# 06_-_NEON.net
KiCad netlist of a schematic drawn in Altium Designer
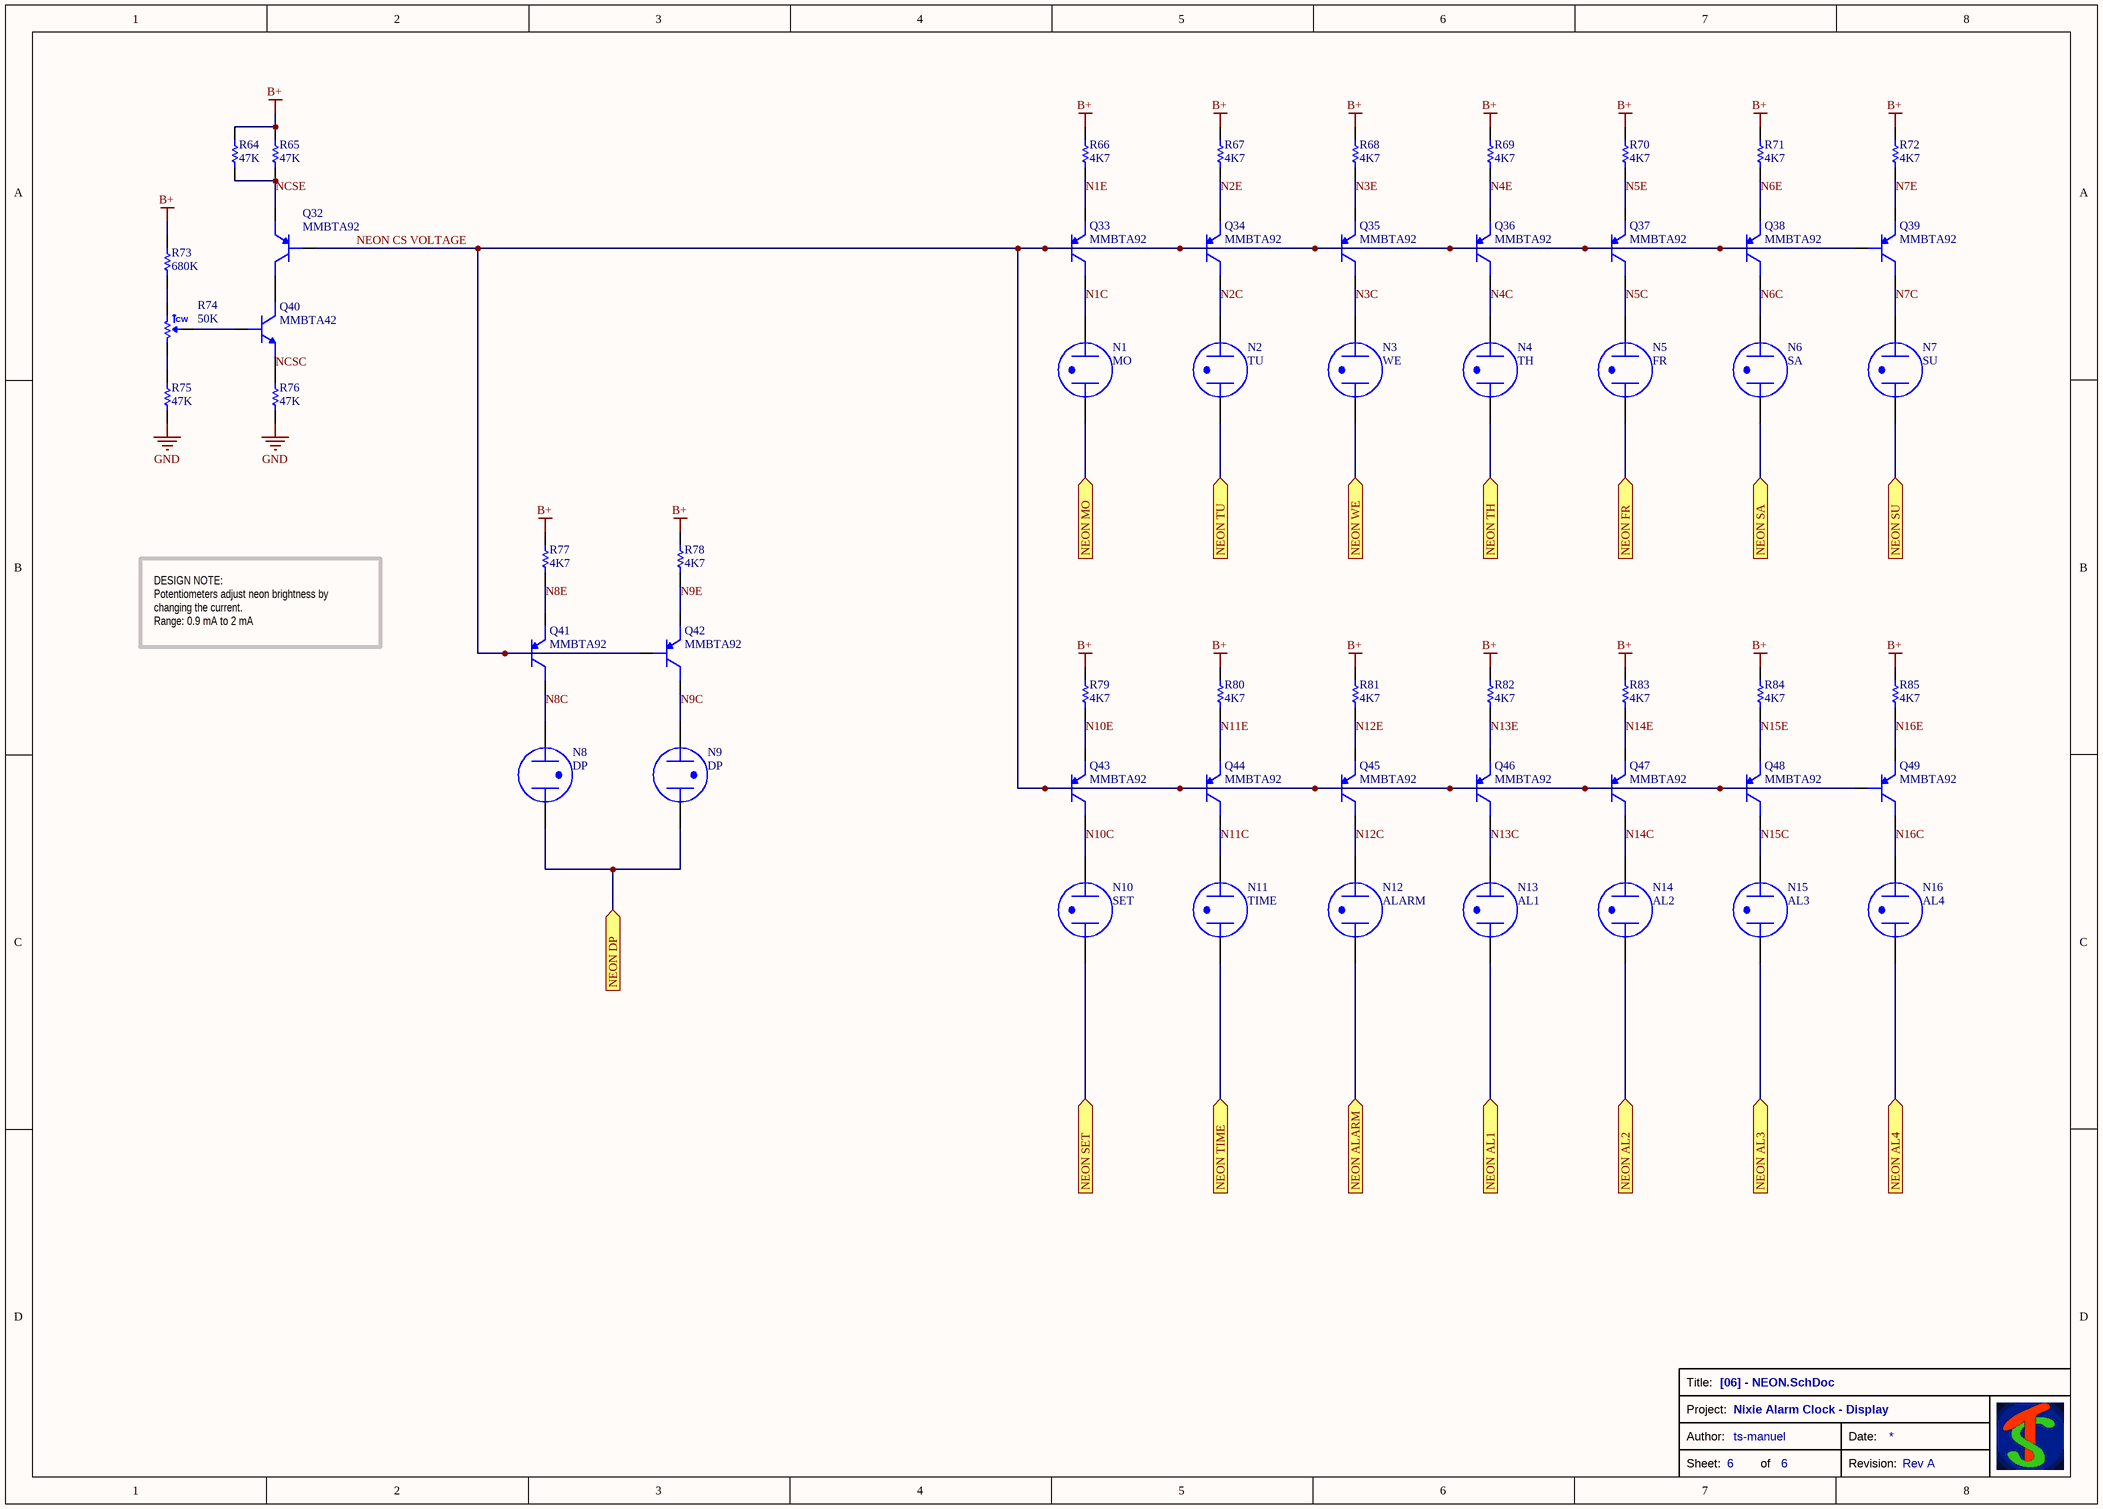
[diagram p0: [06] - NEON.SchDoc]

(export (version "E")
  (design (tool "Eeschema 10.0.6"))
  (components
    (comp (ref "N1")
      (value "MO")
      (footprint "NE4 NEON LAMP")
      (description "Lampade Std. Brightness Neon Lamp Tin Leads")
      (libsource (lib "mt_local_library") (part "T4-NEON-LAMP"))
    )
    (comp (ref "N2")
      (value "TU")
      (footprint "NE4 NEON LAMP")
      (description "Lampade Std. Brightness Neon Lamp Tin Leads")
      (libsource (lib "mt_local_library") (part "T4-NEON-LAMP"))
    )
    (comp (ref "N3")
      (value "WE")
      (footprint "NE4 NEON LAMP")
      (description "Lampade Std. Brightness Neon Lamp Tin Leads")
      (libsource (lib "mt_local_library") (part "T4-NEON-LAMP"))
    )
    (comp (ref "N4")
      (value "TH")
      (footprint "NE4 NEON LAMP")
      (description "Lampade Std. Brightness Neon Lamp Tin Leads")
      (libsource (lib "mt_local_library") (part "T4-NEON-LAMP"))
    )
    (comp (ref "N5")
      (value "FR")
      (footprint "NE4 NEON LAMP")
      (description "Lampade Std. Brightness Neon Lamp Tin Leads")
      (libsource (lib "mt_local_library") (part "T4-NEON-LAMP"))
    )
    (comp (ref "N6")
      (value "SA")
      (footprint "NE4 NEON LAMP")
      (description "Lampade Std. Brightness Neon Lamp Tin Leads")
      (libsource (lib "mt_local_library") (part "T4-NEON-LAMP"))
    )
    (comp (ref "N7")
      (value "SU")
      (footprint "NE4 NEON LAMP")
      (description "Lampade Std. Brightness Neon Lamp Tin Leads")
      (libsource (lib "mt_local_library") (part "T4-NEON-LAMP"))
    )
    (comp (ref "N8")
      (value "DP")
      (footprint "NE4 NEON LAMP")
      (description "Lampade Std. Brightness Neon Lamp Tin Leads")
      (libsource (lib "mt_local_library") (part "T4-NEON-LAMP"))
    )
    (comp (ref "N9")
      (value "DP")
      (footprint "NE4 NEON LAMP")
      (description "Lampade Std. Brightness Neon Lamp Tin Leads")
      (libsource (lib "mt_local_library") (part "T4-NEON-LAMP"))
    )
    (comp (ref "N10")
      (value "SET")
      (footprint "NE4 NEON LAMP")
      (description "Lampade Std. Brightness Neon Lamp Tin Leads")
      (libsource (lib "mt_local_library") (part "T4-NEON-LAMP"))
    )
    (comp (ref "N11")
      (value "TIME")
      (footprint "NE4 NEON LAMP")
      (description "Lampade Std. Brightness Neon Lamp Tin Leads")
      (libsource (lib "mt_local_library") (part "T4-NEON-LAMP"))
    )
    (comp (ref "N12")
      (value "ALARM")
      (footprint "NE4 NEON LAMP")
      (description "Lampade Std. Brightness Neon Lamp Tin Leads")
      (libsource (lib "mt_local_library") (part "T4-NEON-LAMP"))
    )
    (comp (ref "N13")
      (value "AL1")
      (footprint "NE4 NEON LAMP")
      (description "Lampade Std. Brightness Neon Lamp Tin Leads")
      (libsource (lib "mt_local_library") (part "T4-NEON-LAMP"))
    )
    (comp (ref "N14")
      (value "AL2")
      (footprint "NE4 NEON LAMP")
      (description "Lampade Std. Brightness Neon Lamp Tin Leads")
      (libsource (lib "mt_local_library") (part "T4-NEON-LAMP"))
    )
    (comp (ref "N15")
      (value "AL3")
      (footprint "NE4 NEON LAMP")
      (description "Lampade Std. Brightness Neon Lamp Tin Leads")
      (libsource (lib "mt_local_library") (part "T4-NEON-LAMP"))
    )
    (comp (ref "N16")
      (value "AL4")
      (footprint "NE4 NEON LAMP")
      (description "Lampade Std. Brightness Neon Lamp Tin Leads")
      (libsource (lib "mt_local_library") (part "T4-NEON-LAMP"))
    )
    (comp (ref "Q32")
      (value "MMBTA92")
      (footprint "SOT95P240X110-3N")
      (description "300V PNP SMALL SIGNAL TRANSISTOR IN SOT23")
      (libsource (lib "mt_local_library") (part "PNP-MMBTA92"))
    )
    (comp (ref "Q33")
      (value "MMBTA92")
      (footprint "SOT95P240X110-3N")
      (description "300V PNP SMALL SIGNAL TRANSISTOR IN SOT23")
      (libsource (lib "mt_local_library") (part "PNP-MMBTA92"))
    )
    (comp (ref "Q34")
      (value "MMBTA92")
      (footprint "SOT95P240X110-3N")
      (description "300V PNP SMALL SIGNAL TRANSISTOR IN SOT23")
      (libsource (lib "mt_local_library") (part "PNP-MMBTA92"))
    )
    (comp (ref "Q35")
      (value "MMBTA92")
      (footprint "SOT95P240X110-3N")
      (description "300V PNP SMALL SIGNAL TRANSISTOR IN SOT23")
      (libsource (lib "mt_local_library") (part "PNP-MMBTA92"))
    )
    (comp (ref "Q36")
      (value "MMBTA92")
      (footprint "SOT95P240X110-3N")
      (description "300V PNP SMALL SIGNAL TRANSISTOR IN SOT23")
      (libsource (lib "mt_local_library") (part "PNP-MMBTA92"))
    )
    (comp (ref "Q37")
      (value "MMBTA92")
      (footprint "SOT95P240X110-3N")
      (description "300V PNP SMALL SIGNAL TRANSISTOR IN SOT23")
      (libsource (lib "mt_local_library") (part "PNP-MMBTA92"))
    )
    (comp (ref "Q38")
      (value "MMBTA92")
      (footprint "SOT95P240X110-3N")
      (description "300V PNP SMALL SIGNAL TRANSISTOR IN SOT23")
      (libsource (lib "mt_local_library") (part "PNP-MMBTA92"))
    )
    (comp (ref "Q39")
      (value "MMBTA92")
      (footprint "SOT95P240X110-3N")
      (description "300V PNP SMALL SIGNAL TRANSISTOR IN SOT23")
      (libsource (lib "mt_local_library") (part "PNP-MMBTA92"))
    )
    (comp (ref "Q40")
      (value "MMBTA42")
      (footprint "SOT95P240X110-3N")
      (description "300V NPN SMALL SIGNAL TRANSISTOR IN SOT23")
      (libsource (lib "mt_local_library") (part "NPN-MMBTA42"))
    )
    (comp (ref "Q41")
      (value "MMBTA92")
      (footprint "SOT95P240X110-3N")
      (description "300V PNP SMALL SIGNAL TRANSISTOR IN SOT23")
      (libsource (lib "mt_local_library") (part "PNP-MMBTA92"))
    )
    (comp (ref "Q42")
      (value "MMBTA92")
      (footprint "SOT95P240X110-3N")
      (description "300V PNP SMALL SIGNAL TRANSISTOR IN SOT23")
      (libsource (lib "mt_local_library") (part "PNP-MMBTA92"))
    )
    (comp (ref "Q43")
      (value "MMBTA92")
      (footprint "SOT95P240X110-3N")
      (description "300V PNP SMALL SIGNAL TRANSISTOR IN SOT23")
      (libsource (lib "mt_local_library") (part "PNP-MMBTA92"))
    )
    (comp (ref "Q44")
      (value "MMBTA92")
      (footprint "SOT95P240X110-3N")
      (description "300V PNP SMALL SIGNAL TRANSISTOR IN SOT23")
      (libsource (lib "mt_local_library") (part "PNP-MMBTA92"))
    )
    (comp (ref "Q45")
      (value "MMBTA92")
      (footprint "SOT95P240X110-3N")
      (description "300V PNP SMALL SIGNAL TRANSISTOR IN SOT23")
      (libsource (lib "mt_local_library") (part "PNP-MMBTA92"))
    )
    (comp (ref "Q46")
      (value "MMBTA92")
      (footprint "SOT95P240X110-3N")
      (description "300V PNP SMALL SIGNAL TRANSISTOR IN SOT23")
      (libsource (lib "mt_local_library") (part "PNP-MMBTA92"))
    )
    (comp (ref "Q47")
      (value "MMBTA92")
      (footprint "SOT95P240X110-3N")
      (description "300V PNP SMALL SIGNAL TRANSISTOR IN SOT23")
      (libsource (lib "mt_local_library") (part "PNP-MMBTA92"))
    )
    (comp (ref "Q48")
      (value "MMBTA92")
      (footprint "SOT95P240X110-3N")
      (description "300V PNP SMALL SIGNAL TRANSISTOR IN SOT23")
      (libsource (lib "mt_local_library") (part "PNP-MMBTA92"))
    )
    (comp (ref "Q49")
      (value "MMBTA92")
      (footprint "SOT95P240X110-3N")
      (description "300V PNP SMALL SIGNAL TRANSISTOR IN SOT23")
      (libsource (lib "mt_local_library") (part "PNP-MMBTA92"))
    )
    (comp (ref "R64")
      (value "47K")
      (footprint "RES-0805")
      (description "Thin Film Resistors 1/8W 47K ohm 1% 50ppm")
      (fields (field (name "MANUFACTURER") "Yageo") (field (name "TOLERANCE") "1%"))
      (libsource (lib "mt_local_library") (part "RES-0805-47K-RT0805FRE0747KL"))
    )
    (comp (ref "R65")
      (value "47K")
      (footprint "RES-0805")
      (description "Thin Film Resistors 1/8W 47K ohm 1% 50ppm")
      (fields (field (name "MANUFACTURER") "Yageo") (field (name "TOLERANCE") "1%"))
      (libsource (lib "mt_local_library") (part "RES-0805-47K-RT0805FRE0747KL"))
    )
    (comp (ref "R66")
      (value "4K7")
      (footprint "RES-0805")
      (description "Thin Film Resistors 4.7K ohm 1% 50 ppm")
      (fields (field (name "MANUFACTURER") "Yageo") (field (name "TOLERANCE") "1%"))
      (libsource (lib "mt_local_library") (part "RES-0805-4K7-RT0805FRE134K7L"))
    )
    (comp (ref "R67")
      (value "4K7")
      (footprint "RES-0805")
      (description "Thin Film Resistors 4.7K ohm 1% 50 ppm")
      (fields (field (name "MANUFACTURER") "Yageo") (field (name "TOLERANCE") "1%"))
      (libsource (lib "mt_local_library") (part "RES-0805-4K7-RT0805FRE134K7L"))
    )
    (comp (ref "R68")
      (value "4K7")
      (footprint "RES-0805")
      (description "Thin Film Resistors 4.7K ohm 1% 50 ppm")
      (fields (field (name "MANUFACTURER") "Yageo") (field (name "TOLERANCE") "1%"))
      (libsource (lib "mt_local_library") (part "RES-0805-4K7-RT0805FRE134K7L"))
    )
    (comp (ref "R69")
      (value "4K7")
      (footprint "RES-0805")
      (description "Thin Film Resistors 4.7K ohm 1% 50 ppm")
      (fields (field (name "MANUFACTURER") "Yageo") (field (name "TOLERANCE") "1%"))
      (libsource (lib "mt_local_library") (part "RES-0805-4K7-RT0805FRE134K7L"))
    )
    (comp (ref "R70")
      (value "4K7")
      (footprint "RES-0805")
      (description "Thin Film Resistors 4.7K ohm 1% 50 ppm")
      (fields (field (name "MANUFACTURER") "Yageo") (field (name "TOLERANCE") "1%"))
      (libsource (lib "mt_local_library") (part "RES-0805-4K7-RT0805FRE134K7L"))
    )
    (comp (ref "R71")
      (value "4K7")
      (footprint "RES-0805")
      (description "Thin Film Resistors 4.7K ohm 1% 50 ppm")
      (fields (field (name "MANUFACTURER") "Yageo") (field (name "TOLERANCE") "1%"))
      (libsource (lib "mt_local_library") (part "RES-0805-4K7-RT0805FRE134K7L"))
    )
    (comp (ref "R72")
      (value "4K7")
      (footprint "RES-0805")
      (description "Thin Film Resistors 4.7K ohm 1% 50 ppm")
      (fields (field (name "MANUFACTURER") "Yageo") (field (name "TOLERANCE") "1%"))
      (libsource (lib "mt_local_library") (part "RES-0805-4K7-RT0805FRE134K7L"))
    )
    (comp (ref "R73")
      (value "680K")
      (footprint "RES-1206")
      (description "Thin Film Resistors 680K OHM 1% 50PPM 1/4W")
      (fields (field (name "MANUFACTURER") "Yageo") (field (name "TOLERANCE") "1%"))
      (libsource (lib "mt_local_library") (part "RES-1206-680K-RT1206FRE07680KL"))
    )
    (comp (ref "R74")
      (value "50K")
      (footprint "TC33X2503E")
      (description "Resistenze trimmer - SMD 3MM 50KOHMS 25% 0.1WATT OPEN FRM")
      (fields (field (name "MANUFACTURER") "Yageo") (field (name "TOLERANCE") "1%"))
      (libsource (lib "mt_local_library") (part "POT-50K-TC33X-2-503E"))
    )
    (comp (ref "R75")
      (value "47K")
      (footprint "RES-0805")
      (description "Thin Film Resistors 1/8W 47K ohm 1% 50ppm")
      (fields (field (name "MANUFACTURER") "Yageo") (field (name "TOLERANCE") "1%"))
      (libsource (lib "mt_local_library") (part "RES-0805-47K-RT0805FRE0747KL"))
    )
    (comp (ref "R76")
      (value "47K")
      (footprint "RES-0805")
      (description "Thin Film Resistors 1/8W 47K ohm 1% 50ppm")
      (fields (field (name "MANUFACTURER") "Yageo") (field (name "TOLERANCE") "1%"))
      (libsource (lib "mt_local_library") (part "RES-0805-47K-RT0805FRE0747KL"))
    )
    (comp (ref "R77")
      (value "4K7")
      (footprint "RES-0805")
      (description "Thin Film Resistors 4.7K ohm 1% 50 ppm")
      (fields (field (name "MANUFACTURER") "Yageo") (field (name "TOLERANCE") "1%"))
      (libsource (lib "mt_local_library") (part "RES-0805-4K7-RT0805FRE134K7L"))
    )
    (comp (ref "R78")
      (value "4K7")
      (footprint "RES-0805")
      (description "Thin Film Resistors 4.7K ohm 1% 50 ppm")
      (fields (field (name "MANUFACTURER") "Yageo") (field (name "TOLERANCE") "1%"))
      (libsource (lib "mt_local_library") (part "RES-0805-4K7-RT0805FRE134K7L"))
    )
    (comp (ref "R79")
      (value "4K7")
      (footprint "RES-0805")
      (description "Thin Film Resistors 4.7K ohm 1% 50 ppm")
      (fields (field (name "MANUFACTURER") "Yageo") (field (name "TOLERANCE") "1%"))
      (libsource (lib "mt_local_library") (part "RES-0805-4K7-RT0805FRE134K7L"))
    )
    (comp (ref "R80")
      (value "4K7")
      (footprint "RES-0805")
      (description "Thin Film Resistors 4.7K ohm 1% 50 ppm")
      (fields (field (name "MANUFACTURER") "Yageo") (field (name "TOLERANCE") "1%"))
      (libsource (lib "mt_local_library") (part "RES-0805-4K7-RT0805FRE134K7L"))
    )
    (comp (ref "R81")
      (value "4K7")
      (footprint "RES-0805")
      (description "Thin Film Resistors 4.7K ohm 1% 50 ppm")
      (fields (field (name "MANUFACTURER") "Yageo") (field (name "TOLERANCE") "1%"))
      (libsource (lib "mt_local_library") (part "RES-0805-4K7-RT0805FRE134K7L"))
    )
    (comp (ref "R82")
      (value "4K7")
      (footprint "RES-0805")
      (description "Thin Film Resistors 4.7K ohm 1% 50 ppm")
      (fields (field (name "MANUFACTURER") "Yageo") (field (name "TOLERANCE") "1%"))
      (libsource (lib "mt_local_library") (part "RES-0805-4K7-RT0805FRE134K7L"))
    )
    (comp (ref "R83")
      (value "4K7")
      (footprint "RES-0805")
      (description "Thin Film Resistors 4.7K ohm 1% 50 ppm")
      (fields (field (name "MANUFACTURER") "Yageo") (field (name "TOLERANCE") "1%"))
      (libsource (lib "mt_local_library") (part "RES-0805-4K7-RT0805FRE134K7L"))
    )
    (comp (ref "R84")
      (value "4K7")
      (footprint "RES-0805")
      (description "Thin Film Resistors 4.7K ohm 1% 50 ppm")
      (fields (field (name "MANUFACTURER") "Yageo") (field (name "TOLERANCE") "1%"))
      (libsource (lib "mt_local_library") (part "RES-0805-4K7-RT0805FRE134K7L"))
    )
    (comp (ref "R85")
      (value "4K7")
      (footprint "RES-0805")
      (description "Thin Film Resistors 4.7K ohm 1% 50 ppm")
      (fields (field (name "MANUFACTURER") "Yageo") (field (name "TOLERANCE") "1%"))
      (libsource (lib "mt_local_library") (part "RES-0805-4K7-RT0805FRE134K7L"))
    )
  )
  (nets
    (net (code "1") (name "/N1C") (class "Default")
      (node (ref "N1") (pin "2") (pinfunction "2_2") (pintype "passive"))
      (node (ref "Q33") (pin "3") (pinfunction "C_3") (pintype "passive"))
    )
    (net (code "2") (name "/N1E") (class "Default")
      (node (ref "Q33") (pin "2") (pinfunction "E_2") (pintype "passive"))
      (node (ref "R66") (pin "1") (pinfunction "1_1") (pintype "passive"))
    )
    (net (code "3") (name "/N2C") (class "Default")
      (node (ref "N2") (pin "2") (pinfunction "2_2") (pintype "passive"))
      (node (ref "Q34") (pin "3") (pinfunction "C_3") (pintype "passive"))
    )
    (net (code "4") (name "/N2E") (class "Default")
      (node (ref "Q34") (pin "2") (pinfunction "E_2") (pintype "passive"))
      (node (ref "R67") (pin "1") (pinfunction "1_1") (pintype "passive"))
    )
    (net (code "5") (name "/N3C") (class "Default")
      (node (ref "N3") (pin "2") (pinfunction "2_2") (pintype "passive"))
      (node (ref "Q35") (pin "3") (pinfunction "C_3") (pintype "passive"))
    )
    (net (code "6") (name "/N3E") (class "Default")
      (node (ref "Q35") (pin "2") (pinfunction "E_2") (pintype "passive"))
      (node (ref "R68") (pin "1") (pinfunction "1_1") (pintype "passive"))
    )
    (net (code "7") (name "/N4C") (class "Default")
      (node (ref "N4") (pin "2") (pinfunction "2_2") (pintype "passive"))
      (node (ref "Q36") (pin "3") (pinfunction "C_3") (pintype "passive"))
    )
    (net (code "8") (name "/N4E") (class "Default")
      (node (ref "Q36") (pin "2") (pinfunction "E_2") (pintype "passive"))
      (node (ref "R69") (pin "1") (pinfunction "1_1") (pintype "passive"))
    )
    (net (code "9") (name "/N5C") (class "Default")
      (node (ref "N5") (pin "2") (pinfunction "2_2") (pintype "passive"))
      (node (ref "Q37") (pin "3") (pinfunction "C_3") (pintype "passive"))
    )
    (net (code "10") (name "/N5E") (class "Default")
      (node (ref "Q37") (pin "2") (pinfunction "E_2") (pintype "passive"))
      (node (ref "R70") (pin "1") (pinfunction "1_1") (pintype "passive"))
    )
    (net (code "11") (name "/N6C") (class "Default")
      (node (ref "N6") (pin "2") (pinfunction "2_2") (pintype "passive"))
      (node (ref "Q38") (pin "3") (pinfunction "C_3") (pintype "passive"))
    )
    (net (code "12") (name "/N6E") (class "Default")
      (node (ref "Q38") (pin "2") (pinfunction "E_2") (pintype "passive"))
      (node (ref "R71") (pin "1") (pinfunction "1_1") (pintype "passive"))
    )
    (net (code "13") (name "/N7C") (class "Default")
      (node (ref "N7") (pin "2") (pinfunction "2_2") (pintype "passive"))
      (node (ref "Q39") (pin "3") (pinfunction "C_3") (pintype "passive"))
    )
    (net (code "14") (name "/N7E") (class "Default")
      (node (ref "Q39") (pin "2") (pinfunction "E_2") (pintype "passive"))
      (node (ref "R72") (pin "1") (pinfunction "1_1") (pintype "passive"))
    )
    (net (code "15") (name "/N8C") (class "Default")
      (node (ref "N8") (pin "1") (pinfunction "1_1") (pintype "passive"))
      (node (ref "Q41") (pin "3") (pinfunction "C_3") (pintype "passive"))
    )
    (net (code "16") (name "/N8E") (class "Default")
      (node (ref "Q41") (pin "2") (pinfunction "E_2") (pintype "passive"))
      (node (ref "R77") (pin "1") (pinfunction "1_1") (pintype "passive"))
    )
    (net (code "17") (name "/N9C") (class "Default")
      (node (ref "N9") (pin "1") (pinfunction "1_1") (pintype "passive"))
      (node (ref "Q42") (pin "3") (pinfunction "C_3") (pintype "passive"))
    )
    (net (code "18") (name "/N9E") (class "Default")
      (node (ref "Q42") (pin "2") (pinfunction "E_2") (pintype "passive"))
      (node (ref "R78") (pin "1") (pinfunction "1_1") (pintype "passive"))
    )
    (net (code "19") (name "/N10C") (class "Default")
      (node (ref "N10") (pin "2") (pinfunction "2_2") (pintype "passive"))
      (node (ref "Q43") (pin "3") (pinfunction "C_3") (pintype "passive"))
    )
    (net (code "20") (name "/N10E") (class "Default")
      (node (ref "Q43") (pin "2") (pinfunction "E_2") (pintype "passive"))
      (node (ref "R79") (pin "1") (pinfunction "1_1") (pintype "passive"))
    )
    (net (code "21") (name "/N11C") (class "Default")
      (node (ref "N11") (pin "2") (pinfunction "2_2") (pintype "passive"))
      (node (ref "Q44") (pin "3") (pinfunction "C_3") (pintype "passive"))
    )
    (net (code "22") (name "/N11E") (class "Default")
      (node (ref "Q44") (pin "2") (pinfunction "E_2") (pintype "passive"))
      (node (ref "R80") (pin "1") (pinfunction "1_1") (pintype "passive"))
    )
    (net (code "23") (name "/N12C") (class "Default")
      (node (ref "N12") (pin "2") (pinfunction "2_2") (pintype "passive"))
      (node (ref "Q45") (pin "3") (pinfunction "C_3") (pintype "passive"))
    )
    (net (code "24") (name "/N12E") (class "Default")
      (node (ref "Q45") (pin "2") (pinfunction "E_2") (pintype "passive"))
      (node (ref "R81") (pin "1") (pinfunction "1_1") (pintype "passive"))
    )
    (net (code "25") (name "/N13C") (class "Default")
      (node (ref "N13") (pin "2") (pinfunction "2_2") (pintype "passive"))
      (node (ref "Q46") (pin "3") (pinfunction "C_3") (pintype "passive"))
    )
    (net (code "26") (name "/N13E") (class "Default")
      (node (ref "Q46") (pin "2") (pinfunction "E_2") (pintype "passive"))
      (node (ref "R82") (pin "1") (pinfunction "1_1") (pintype "passive"))
    )
    (net (code "27") (name "/N14C") (class "Default")
      (node (ref "N14") (pin "2") (pinfunction "2_2") (pintype "passive"))
      (node (ref "Q47") (pin "3") (pinfunction "C_3") (pintype "passive"))
    )
    (net (code "28") (name "/N14E") (class "Default")
      (node (ref "Q47") (pin "2") (pinfunction "E_2") (pintype "passive"))
      (node (ref "R83") (pin "1") (pinfunction "1_1") (pintype "passive"))
    )
    (net (code "29") (name "/N15C") (class "Default")
      (node (ref "N15") (pin "2") (pinfunction "2_2") (pintype "passive"))
      (node (ref "Q48") (pin "3") (pinfunction "C_3") (pintype "passive"))
    )
    (net (code "30") (name "/N15E") (class "Default")
      (node (ref "Q48") (pin "2") (pinfunction "E_2") (pintype "passive"))
      (node (ref "R84") (pin "1") (pinfunction "1_1") (pintype "passive"))
    )
    (net (code "31") (name "/N16C") (class "Default")
      (node (ref "N16") (pin "2") (pinfunction "2_2") (pintype "passive"))
      (node (ref "Q49") (pin "3") (pinfunction "C_3") (pintype "passive"))
    )
    (net (code "32") (name "/N16E") (class "Default")
      (node (ref "Q49") (pin "2") (pinfunction "E_2") (pintype "passive"))
      (node (ref "R85") (pin "1") (pinfunction "1_1") (pintype "passive"))
    )
    (net (code "33") (name "/NCSC") (class "Default")
      (node (ref "Q40") (pin "2") (pinfunction "E_2") (pintype "passive"))
      (node (ref "R76") (pin "2") (pinfunction "2_2") (pintype "passive"))
    )
    (net (code "34") (name "/NCSE") (class "Default")
      (node (ref "Q32") (pin "2") (pinfunction "E_2") (pintype "passive"))
      (node (ref "R64") (pin "1") (pinfunction "1_1") (pintype "passive"))
      (node (ref "R65") (pin "1") (pinfunction "1_1") (pintype "passive"))
    )
    (net (code "35") (name "/NEON AL1") (class "Default")
      (node (ref "N13") (pin "1") (pinfunction "1_1") (pintype "passive"))
    )
    (net (code "36") (name "/NEON AL2") (class "Default")
      (node (ref "N14") (pin "1") (pinfunction "1_1") (pintype "passive"))
    )
    (net (code "37") (name "/NEON AL3") (class "Default")
      (node (ref "N15") (pin "1") (pinfunction "1_1") (pintype "passive"))
    )
    (net (code "38") (name "/NEON AL4") (class "Default")
      (node (ref "N16") (pin "1") (pinfunction "1_1") (pintype "passive"))
    )
    (net (code "39") (name "/NEON ALARM") (class "Default")
      (node (ref "N12") (pin "1") (pinfunction "1_1") (pintype "passive"))
    )
    (net (code "40") (name "/NEON CS VOLTAGE") (class "Default")
      (node (ref "Q32") (pin "1") (pinfunction "B_1") (pintype "passive"))
      (node (ref "Q33") (pin "1") (pinfunction "B_1") (pintype "passive"))
      (node (ref "Q34") (pin "1") (pinfunction "B_1") (pintype "passive"))
      (node (ref "Q35") (pin "1") (pinfunction "B_1") (pintype "passive"))
      (node (ref "Q36") (pin "1") (pinfunction "B_1") (pintype "passive"))
      (node (ref "Q37") (pin "1") (pinfunction "B_1") (pintype "passive"))
      (node (ref "Q38") (pin "1") (pinfunction "B_1") (pintype "passive"))
      (node (ref "Q39") (pin "1") (pinfunction "B_1") (pintype "passive"))
      (node (ref "Q41") (pin "1") (pinfunction "B_1") (pintype "passive"))
      (node (ref "Q42") (pin "1") (pinfunction "B_1") (pintype "passive"))
      (node (ref "Q43") (pin "1") (pinfunction "B_1") (pintype "passive"))
      (node (ref "Q44") (pin "1") (pinfunction "B_1") (pintype "passive"))
      (node (ref "Q45") (pin "1") (pinfunction "B_1") (pintype "passive"))
      (node (ref "Q46") (pin "1") (pinfunction "B_1") (pintype "passive"))
      (node (ref "Q47") (pin "1") (pinfunction "B_1") (pintype "passive"))
      (node (ref "Q48") (pin "1") (pinfunction "B_1") (pintype "passive"))
      (node (ref "Q49") (pin "1") (pinfunction "B_1") (pintype "passive"))
    )
    (net (code "41") (name "/NEON DP") (class "Default")
      (node (ref "N8") (pin "2") (pinfunction "2_2") (pintype "passive"))
      (node (ref "N9") (pin "2") (pinfunction "2_2") (pintype "passive"))
    )
    (net (code "42") (name "/NEON FR") (class "Default")
      (node (ref "N5") (pin "1") (pinfunction "1_1") (pintype "passive"))
    )
    (net (code "43") (name "/NEON MO") (class "Default")
      (node (ref "N1") (pin "1") (pinfunction "1_1") (pintype "passive"))
    )
    (net (code "44") (name "/NEON SA") (class "Default")
      (node (ref "N6") (pin "1") (pinfunction "1_1") (pintype "passive"))
    )
    (net (code "45") (name "/NEON SET") (class "Default")
      (node (ref "N10") (pin "1") (pinfunction "1_1") (pintype "passive"))
    )
    (net (code "46") (name "/NEON SU") (class "Default")
      (node (ref "N7") (pin "1") (pinfunction "1_1") (pintype "passive"))
    )
    (net (code "47") (name "/NEON TH") (class "Default")
      (node (ref "N4") (pin "1") (pinfunction "1_1") (pintype "passive"))
    )
    (net (code "48") (name "/NEON TIME") (class "Default")
      (node (ref "N11") (pin "1") (pinfunction "1_1") (pintype "passive"))
    )
    (net (code "49") (name "/NEON TU") (class "Default")
      (node (ref "N2") (pin "1") (pinfunction "1_1") (pintype "passive"))
    )
    (net (code "50") (name "/NEON WE") (class "Default")
      (node (ref "N3") (pin "1") (pinfunction "1_1") (pintype "passive"))
    )
    (net (code "51") (name "B+") (class "Default")
      (node (ref "R64") (pin "2") (pinfunction "2_2") (pintype "passive"))
      (node (ref "R65") (pin "2") (pinfunction "2_2") (pintype "passive"))
      (node (ref "R66") (pin "2") (pinfunction "2_2") (pintype "passive"))
      (node (ref "R67") (pin "2") (pinfunction "2_2") (pintype "passive"))
      (node (ref "R68") (pin "2") (pinfunction "2_2") (pintype "passive"))
      (node (ref "R69") (pin "2") (pinfunction "2_2") (pintype "passive"))
      (node (ref "R70") (pin "2") (pinfunction "2_2") (pintype "passive"))
      (node (ref "R71") (pin "2") (pinfunction "2_2") (pintype "passive"))
      (node (ref "R72") (pin "2") (pinfunction "2_2") (pintype "passive"))
      (node (ref "R73") (pin "2") (pinfunction "2_2") (pintype "passive"))
      (node (ref "R77") (pin "2") (pinfunction "2_2") (pintype "passive"))
      (node (ref "R78") (pin "2") (pinfunction "2_2") (pintype "passive"))
      (node (ref "R79") (pin "2") (pinfunction "2_2") (pintype "passive"))
      (node (ref "R80") (pin "2") (pinfunction "2_2") (pintype "passive"))
      (node (ref "R81") (pin "2") (pinfunction "2_2") (pintype "passive"))
      (node (ref "R82") (pin "2") (pinfunction "2_2") (pintype "passive"))
      (node (ref "R83") (pin "2") (pinfunction "2_2") (pintype "passive"))
      (node (ref "R84") (pin "2") (pinfunction "2_2") (pintype "passive"))
      (node (ref "R85") (pin "2") (pinfunction "2_2") (pintype "passive"))
    )
    (net (code "52") (name "GND") (class "Default")
      (node (ref "R75") (pin "1") (pinfunction "1_1") (pintype "passive"))
      (node (ref "R76") (pin "1") (pinfunction "1_1") (pintype "passive"))
    )
    (net (code "53") (name "Net-(Q32-C)") (class "Default")
      (node (ref "Q32") (pin "3") (pinfunction "C_3") (pintype "passive"))
      (node (ref "Q40") (pin "3") (pinfunction "C_3") (pintype "passive"))
    )
    (net (code "54") (name "Net-(Q40-B)") (class "Default")
      (node (ref "Q40") (pin "1") (pinfunction "B_1") (pintype "passive"))
      (node (ref "R74") (pin "2") (pinfunction "2_2") (pintype "passive"))
    )
    (net (code "55") (name "Net-(R73-Pad1)") (class "Default")
      (node (ref "R73") (pin "1") (pinfunction "1_1") (pintype "passive"))
      (node (ref "R74") (pin "3") (pinfunction "3_3") (pintype "passive"))
    )
    (net (code "56") (name "Net-(R74-Pad1)") (class "Default")
      (node (ref "R74") (pin "1") (pinfunction "1_1") (pintype "passive"))
      (node (ref "R75") (pin "2") (pinfunction "2_2") (pintype "passive"))
    )
  )
)
